# Famicom_IO_SNES_REV1_5.net
KiCad netlist of a schematic drawn in EAGLE
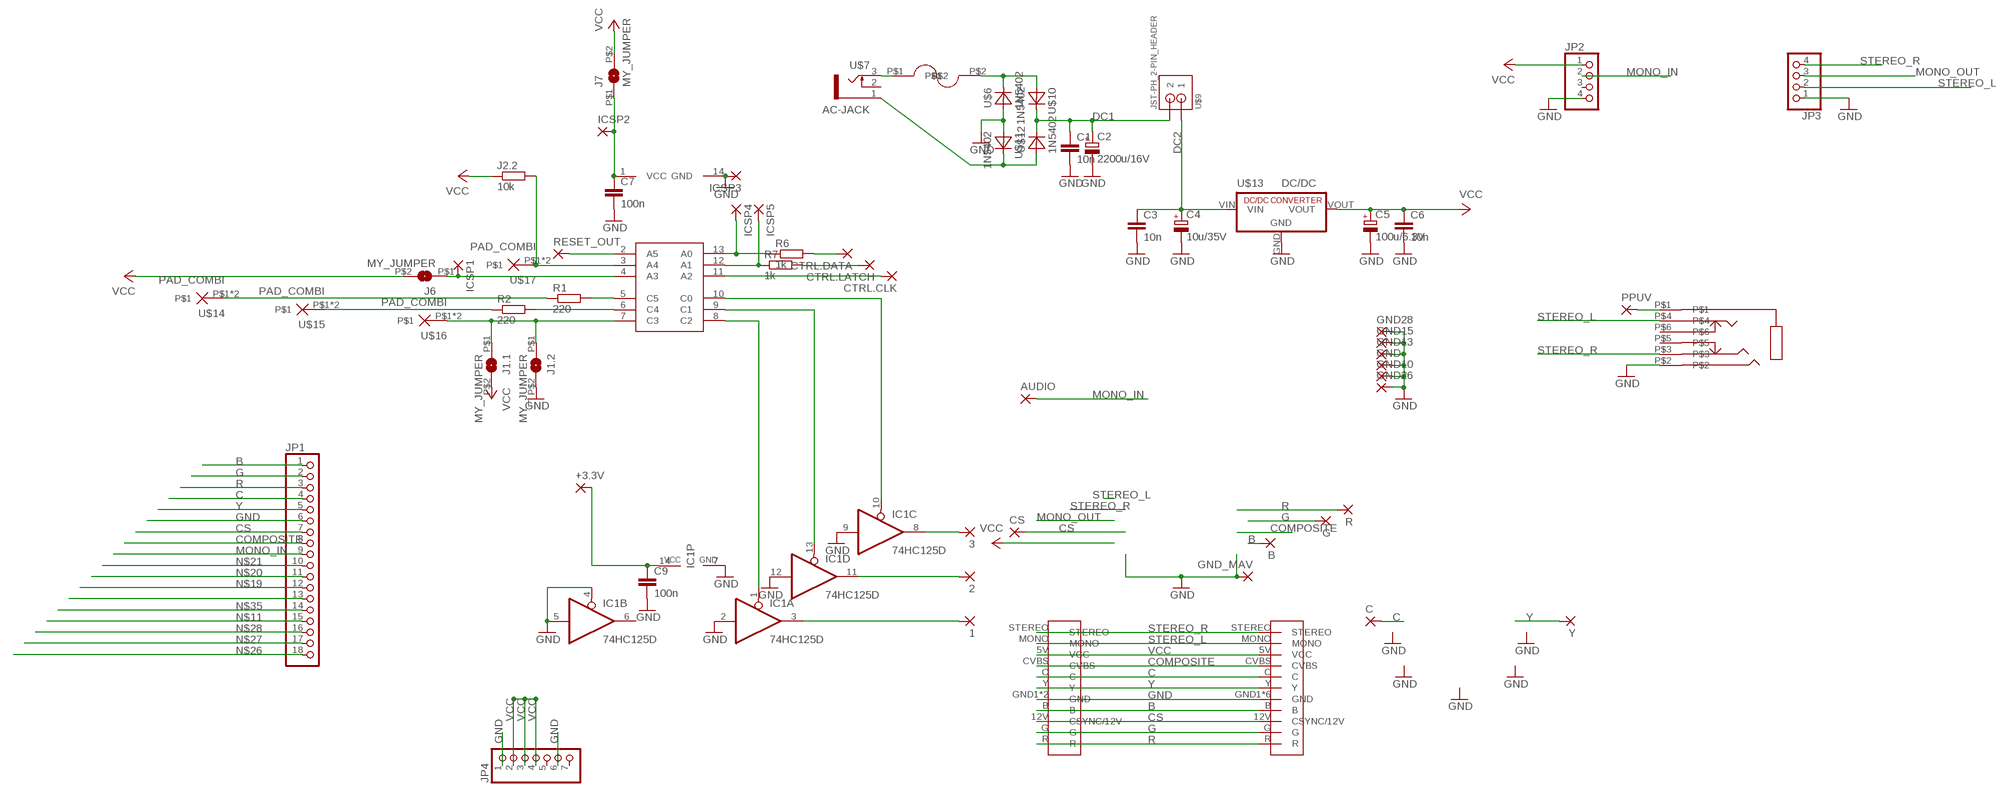
[diagram p0: schematic, sheet 1]

(export (version "E")
  (design (tool "Eeschema 10.0.6"))
  (components
    (comp (ref "+3.3V")
      (value "SMD2")
      (footprint "eagle-import:SMD1,27-2,54")
      (libsource (lib "eagle-import") (part "SMD2"))
    )
    (comp (ref "1")
      (value "SMD2")
      (footprint "eagle-import:SMD1,27-2,54")
      (libsource (lib "eagle-import") (part "SMD2"))
    )
    (comp (ref "2")
      (value "SMD2")
      (footprint "eagle-import:SMD1,27-2,54")
      (libsource (lib "eagle-import") (part "SMD2"))
    )
    (comp (ref "3")
      (value "SMD2")
      (footprint "eagle-import:SMD1,27-2,54")
      (libsource (lib "eagle-import") (part "SMD2"))
    )
    (comp (ref "AUDIO")
      (value "SMD2")
      (footprint "eagle-import:SMD1,27-2,54")
      (libsource (lib "eagle-import") (part "SMD2"))
    )
    (comp (ref "B")
      (value "SMD2")
      (footprint "eagle-import:SMD1,27-2,54")
      (libsource (lib "eagle-import") (part "SMD2"))
    )
    (comp (ref "C")
      (value "SMD2")
      (footprint "eagle-import:SMD1,27-2,54")
      (libsource (lib "eagle-import") (part "SMD2"))
    )
    (comp (ref "C1")
      (value "10n")
      (footprint "eagle-import:Z0805")
      (libsource (lib "eagle-import") (part "C0805"))
    )
    (comp (ref "C2")
      (value "2200u/16V")
      (footprint "eagle-import:E5-13")
      (libsource (lib "eagle-import") (part "resistor_CPOL-EUE5-13"))
    )
    (comp (ref "C3")
      (value "10n")
      (footprint "eagle-import:Z0805")
      (libsource (lib "eagle-import") (part "C0805"))
    )
    (comp (ref "C4")
      (value "10u/35V")
      (footprint "eagle-import:PANASONIC_B")
      (libsource (lib "eagle-import") (part "CPOL-EUB"))
    )
    (comp (ref "C5")
      (value "100u/6.3V")
      (footprint "eagle-import:PANASONIC_D")
      (libsource (lib "eagle-import") (part "CPOL-EUD"))
    )
    (comp (ref "C6")
      (value "10n")
      (footprint "eagle-import:Z0805")
      (libsource (lib "eagle-import") (part "C0805"))
    )
    (comp (ref "C7")
      (value "100n")
      (footprint "eagle-import:Z0805")
      (libsource (lib "eagle-import") (part "C0805"))
    )
    (comp (ref "C9")
      (value "100n")
      (footprint "eagle-import:Z0805")
      (libsource (lib "eagle-import") (part "C0805"))
    )
    (comp (ref "CS")
      (value "SMD2")
      (footprint "eagle-import:SMD1,27-2,54")
      (libsource (lib "eagle-import") (part "SMD2"))
    )
    (comp (ref "CTRL.CLK")
      (value "SMD2")
      (footprint "eagle-import:SMD1,27-2,54")
      (libsource (lib "eagle-import") (part "SMD2"))
    )
    (comp (ref "CTRL.DATA")
      (value "SMD2")
      (footprint "eagle-import:SMD1,27-2,54")
      (libsource (lib "eagle-import") (part "SMD2"))
    )
    (comp (ref "CTRL.LATCH")
      (value "SMD2")
      (footprint "eagle-import:SMD1,27-2,54")
      (libsource (lib "eagle-import") (part "SMD2"))
    )
    (comp (ref "G")
      (value "SMD2")
      (footprint "eagle-import:SMD1,27-2,54")
      (libsource (lib "eagle-import") (part "SMD2"))
    )
    (comp (ref "GND")
      (value "SMD5")
      (footprint "eagle-import:SMD2,54-5,08")
      (libsource (lib "eagle-import") (part "SMD5"))
    )
    (comp (ref "GND10")
      (value "SMD5")
      (footprint "eagle-import:SMD2,54-5,08")
      (libsource (lib "eagle-import") (part "SMD5"))
    )
    (comp (ref "GND13")
      (value "SMD5")
      (footprint "eagle-import:SMD2,54-5,08")
      (libsource (lib "eagle-import") (part "SMD5"))
    )
    (comp (ref "GND15")
      (value "SMD5")
      (footprint "eagle-import:SMD2,54-5,08")
      (libsource (lib "eagle-import") (part "SMD5"))
    )
    (comp (ref "GND26")
      (value "SMD5")
      (footprint "eagle-import:SMD2,54-5,08")
      (libsource (lib "eagle-import") (part "SMD5"))
    )
    (comp (ref "GND28")
      (value "SMD5")
      (footprint "eagle-import:SMD2,54-5,08")
      (libsource (lib "eagle-import") (part "SMD5"))
    )
    (comp (ref "GND_MAV")
      (value "SMD2")
      (footprint "eagle-import:SMD1,27-2,54")
      (libsource (lib "eagle-import") (part "SMD2"))
    )
    (comp (ref "IC1")
      (value "74HC125D")
      (footprint "eagle-import:SO14")
      (libsource (lib "eagle-import") (part "74125DHC"))
    )
    (comp (ref "ICSP1")
      (value "1,6/0,8")
      (footprint "eagle-import:1,6_0,8")
      (libsource (lib "eagle-import") (part "1,6/0,8"))
    )
    (comp (ref "ICSP2")
      (value "1,6/0,8")
      (footprint "eagle-import:1,6_0,8")
      (libsource (lib "eagle-import") (part "1,6/0,8"))
    )
    (comp (ref "ICSP3")
      (value "1,6/0,8")
      (footprint "eagle-import:1,6_0,8")
      (libsource (lib "eagle-import") (part "1,6/0,8"))
    )
    (comp (ref "ICSP4")
      (value "1,6/0,8")
      (footprint "eagle-import:1,6_0,8")
      (libsource (lib "eagle-import") (part "1,6/0,8"))
    )
    (comp (ref "ICSP5")
      (value "1,6/0,8")
      (footprint "eagle-import:1,6_0,8")
      (libsource (lib "eagle-import") (part "1,6/0,8"))
    )
    (comp (ref "J1.1")
      (value "MY_JUMPER")
      (footprint "eagle-import:MYJUMP")
      (libsource (lib "eagle-import") (part "MY_JUMPER"))
    )
    (comp (ref "J1.2")
      (value "MY_JUMPER")
      (footprint "eagle-import:MYJUMP")
      (libsource (lib "eagle-import") (part "MY_JUMPER"))
    )
    (comp (ref "J2.2")
      (value "10k")
      (footprint "eagle-import:Z0805")
      (libsource (lib "eagle-import") (part "R0805"))
    )
    (comp (ref "J6")
      (value "MY_JUMPER")
      (footprint "eagle-import:MYJUMP")
      (libsource (lib "eagle-import") (part "MY_JUMPER"))
    )
    (comp (ref "J7")
      (value "MY_JUMPER")
      (footprint "eagle-import:MYJUMP")
      (libsource (lib "eagle-import") (part "MY_JUMPER"))
    )
    (comp (ref "JP1")
      (value "PINHD-1X18_2.00")
      (footprint "eagle-import:1X18M")
      (libsource (lib "eagle-import") (part "PINHD-1X18_2.00"))
    )
    (comp (ref "JP2")
      (value "PINHD-1X04_2.54-S")
      (footprint "eagle-import:1X04-S")
      (libsource (lib "eagle-import") (part "PINHD-1X04_2.54-S"))
    )
    (comp (ref "JP3")
      (value "PINHD-1X04_2.54-S")
      (footprint "eagle-import:1X04-S")
      (libsource (lib "eagle-import") (part "PINHD-1X04_2.54-S"))
    )
    (comp (ref "JP4")
      (value "PINHD-1X07_2.54-S")
      (footprint "eagle-import:1X07-S")
      (libsource (lib "eagle-import") (part "PINHD-1X07_2.54-S"))
    )
    (comp (ref "PPUV")
      (value "SMD2")
      (footprint "eagle-import:SMD1,27-2,54")
      (libsource (lib "eagle-import") (part "SMD2"))
    )
    (comp (ref "R")
      (value "SMD2")
      (footprint "eagle-import:SMD1,27-2,54")
      (libsource (lib "eagle-import") (part "SMD2"))
    )
    (comp (ref "R1")
      (value "220")
      (footprint "eagle-import:Z0805")
      (libsource (lib "eagle-import") (part "R0805"))
    )
    (comp (ref "R2")
      (value "220")
      (footprint "eagle-import:Z0805")
      (libsource (lib "eagle-import") (part "R0805"))
    )
    (comp (ref "R6")
      (value "1k")
      (footprint "eagle-import:Z0805")
      (libsource (lib "eagle-import") (part "R0805"))
    )
    (comp (ref "R7")
      (value "1k")
      (footprint "eagle-import:Z0805")
      (libsource (lib "eagle-import") (part "R0805"))
    )
    (comp (ref "RESET_OUT")
      (value "SMD2")
      (footprint "eagle-import:SMD1,27-2,54")
      (libsource (lib "eagle-import") (part "SMD2"))
    )
    (comp (ref "U$2")
      (value "FUSEHOLDER")
      (footprint "eagle-import:FUSEHOLDER")
      (libsource (lib "eagle-import") (part "FUSEHOLDER"))
    )
    (comp (ref "U$5")
      (value "PIC16F630_SIMPLE")
      (footprint "eagle-import:PIC16F630")
      (libsource (lib "eagle-import") (part "PIC16F630_SIMPLE"))
    )
    (comp (ref "U$6")
      (value "1N5402")
      (footprint "eagle-import:DO201")
      (libsource (lib "eagle-import") (part "1N5402"))
    )
    (comp (ref "U$7")
      (value "AC-JACK")
      (footprint "eagle-import:AC-JACK")
      (libsource (lib "eagle-import") (part "AC-JACK"))
    )
    (comp (ref "U$8")
      (value "PJ-342D")
      (footprint "eagle-import:PJ-342")
      (libsource (lib "eagle-import") (part "PJ-342D"))
    )
    (comp (ref "U$9")
      (value "JST-PH_2-PIN_HEADER")
      (footprint "eagle-import:JST_B2B-PH_HEADER")
      (libsource (lib "eagle-import") (part "JST-PH_2-PIN_HEADER"))
    )
    (comp (ref "U$10")
      (value "1N5402")
      (footprint "eagle-import:DO201")
      (libsource (lib "eagle-import") (part "1N5402"))
    )
    (comp (ref "U$11")
      (value "1N5402")
      (footprint "eagle-import:DO201")
      (libsource (lib "eagle-import") (part "1N5402"))
    )
    (comp (ref "U$12")
      (value "1N5402")
      (footprint "eagle-import:DO201")
      (libsource (lib "eagle-import") (part "1N5402"))
    )
    (comp (ref "U$13")
      (value "DC/DC")
      (footprint "eagle-import:RECOM")
      (libsource (lib "eagle-import") (part "DC/DC"))
    )
    (comp (ref "U$14")
      (value "PAD_COMBI")
      (footprint "eagle-import:PAD_COMBI")
      (libsource (lib "eagle-import") (part "PAD_COMBI"))
    )
    (comp (ref "U$15")
      (value "PAD_COMBI")
      (footprint "eagle-import:PAD_COMBI")
      (libsource (lib "eagle-import") (part "PAD_COMBI"))
    )
    (comp (ref "U$16")
      (value "PAD_COMBI")
      (footprint "eagle-import:PAD_COMBI")
      (libsource (lib "eagle-import") (part "PAD_COMBI"))
    )
    (comp (ref "U$17")
      (value "PAD_COMBI")
      (footprint "eagle-import:PAD_COMBI")
      (libsource (lib "eagle-import") (part "PAD_COMBI"))
    )
    (comp (ref "U$19")
      (value "GC-MULTIAV")
      (footprint "eagle-import:GC-MULTIAV")
      (libsource (lib "eagle-import") (part "GC-MULTIAV"))
    )
    (comp (ref "U$20")
      (value "SNES-MULTIAV2")
      (footprint "eagle-import:SNES-MULTIAV2")
      (libsource (lib "eagle-import") (part "SNES-MULTIAV2"))
    )
    (comp (ref "Y")
      (value "SMD2")
      (footprint "eagle-import:SMD1,27-2,54")
      (libsource (lib "eagle-import") (part "SMD2"))
    )
  )
  (nets
    (net (code "1") (name "/B") (class "Default")
      (node (ref "B") (pin "1") (pinfunction "P_1") (pintype "passive"))
      (node (ref "JP1") (pin "1") (pinfunction "1_1") (pintype "passive"))
      (node (ref "U$19") (pin "B") (pinfunction "B_B") (pintype "output"))
      (node (ref "U$20") (pin "B") (pinfunction "B_B") (pintype "output"))
    )
    (net (code "2") (name "/C") (class "Default")
      (node (ref "C") (pin "1") (pinfunction "P_1") (pintype "passive"))
      (node (ref "JP1") (pin "4") (pinfunction "4_4") (pintype "passive"))
      (node (ref "U$19") (pin "C") (pinfunction "C_C") (pintype "output"))
      (node (ref "U$20") (pin "C") (pinfunction "C_C") (pintype "output"))
    )
    (net (code "3") (name "/COMPOSITE") (class "Default")
      (node (ref "JP1") (pin "8") (pinfunction "8_8") (pintype "passive"))
      (node (ref "PPUV") (pin "1") (pinfunction "P_1") (pintype "passive"))
      (node (ref "U$19") (pin "CVBS") (pinfunction "CVBS_CVBS") (pintype "output"))
      (node (ref "U$20") (pin "CVBS") (pinfunction "CVBS_CVBS") (pintype "output"))
      (node (ref "U$8") (pin "P$1") (pinfunction "P$1_P$1") (pintype "bidirectional"))
    )
    (net (code "4") (name "/CS") (class "Default")
      (node (ref "CS") (pin "1") (pinfunction "P_1") (pintype "passive"))
      (node (ref "JP1") (pin "7") (pinfunction "7_7") (pintype "passive"))
      (node (ref "U$19") (pin "12V") (pinfunction "CSYNC/12V_12V") (pintype "output"))
      (node (ref "U$20") (pin "12V") (pinfunction "CSYNC/12V_12V") (pintype "output"))
    )
    (net (code "5") (name "/DC1") (class "Default")
      (node (ref "C1") (pin "1") (pinfunction "1_1") (pintype "passive"))
      (node (ref "C2") (pin "+") (pinfunction "+_+") (pintype "passive"))
      (node (ref "U$10") (pin "C") (pinfunction "C_C") (pintype "passive"))
      (node (ref "U$12") (pin "C") (pinfunction "C_C") (pintype "passive"))
      (node (ref "U$9") (pin "P2") (pinfunction "2_P2") (pintype "bidirectional"))
    )
    (net (code "6") (name "/DC2") (class "Default")
      (node (ref "C3") (pin "1") (pinfunction "1_1") (pintype "passive"))
      (node (ref "C4") (pin "+") (pinfunction "+_+") (pintype "passive"))
      (node (ref "U$13") (pin "VIN") (pinfunction "VIN_VIN") (pintype "passive"))
      (node (ref "U$9") (pin "P1") (pinfunction "1_P1") (pintype "bidirectional"))
    )
    (net (code "7") (name "/G") (class "Default")
      (node (ref "G") (pin "1") (pinfunction "P_1") (pintype "passive"))
      (node (ref "JP1") (pin "2") (pinfunction "2_2") (pintype "passive"))
      (node (ref "U$19") (pin "G") (pinfunction "G_G") (pintype "output"))
      (node (ref "U$20") (pin "G") (pinfunction "G_G") (pintype "output"))
    )
    (net (code "8") (name "/MONO_IN") (class "Default")
      (node (ref "AUDIO") (pin "1") (pinfunction "P_1") (pintype "passive"))
      (node (ref "JP1") (pin "9") (pinfunction "9_9") (pintype "passive"))
      (node (ref "JP2") (pin "2") (pinfunction "2_2") (pintype "passive"))
    )
    (net (code "9") (name "/MONO_OUT") (class "Default")
      (node (ref "JP3") (pin "3") (pinfunction "3_3") (pintype "passive"))
    )
    (net (code "10") (name "/N$11") (class "Default")
      (node (ref "3") (pin "1") (pinfunction "P_1") (pintype "passive"))
      (node (ref "IC1") (pin "8") (pinfunction "O_8") (pintype "tri_state"))
      (node (ref "JP1") (pin "15") (pinfunction "15_15") (pintype "passive"))
    )
    (net (code "11") (name "/N$19") (class "Default")
      (node (ref "CTRL.DATA") (pin "1") (pinfunction "P_1") (pintype "passive"))
      (node (ref "JP1") (pin "12") (pinfunction "12_12") (pintype "passive"))
      (node (ref "R6") (pin "2") (pinfunction "2_2") (pintype "passive"))
    )
    (net (code "12") (name "/N$20") (class "Default")
      (node (ref "CTRL.LATCH") (pin "1") (pinfunction "P_1") (pintype "passive"))
      (node (ref "JP1") (pin "11") (pinfunction "11_11") (pintype "passive"))
      (node (ref "R7") (pin "2") (pinfunction "2_2") (pintype "passive"))
    )
    (net (code "13") (name "/N$21") (class "Default")
      (node (ref "CTRL.CLK") (pin "1") (pinfunction "P_1") (pintype "passive"))
      (node (ref "JP1") (pin "10") (pinfunction "10_10") (pintype "passive"))
      (node (ref "U$5") (pin "11") (pinfunction "A2_11") (pintype "bidirectional"))
    )
    (net (code "14") (name "/N$26") (class "Default")
      (node (ref "+3.3V") (pin "1") (pinfunction "P_1") (pintype "passive"))
      (node (ref "C9") (pin "1") (pinfunction "1_1") (pintype "passive"))
      (node (ref "IC1") (pin "14") (pinfunction "VCC_14") (pintype "power_in"))
      (node (ref "JP1") (pin "18") (pinfunction "18_18") (pintype "passive"))
    )
    (net (code "15") (name "/N$27") (class "Default")
      (node (ref "1") (pin "1") (pinfunction "P_1") (pintype "passive"))
      (node (ref "IC1") (pin "3") (pinfunction "O_3") (pintype "tri_state"))
      (node (ref "JP1") (pin "17") (pinfunction "17_17") (pintype "passive"))
    )
    (net (code "16") (name "/N$28") (class "Default")
      (node (ref "2") (pin "1") (pinfunction "P_1") (pintype "passive"))
      (node (ref "IC1") (pin "11") (pinfunction "O_11") (pintype "tri_state"))
      (node (ref "JP1") (pin "16") (pinfunction "16_16") (pintype "passive"))
    )
    (net (code "17") (name "/N$35") (class "Default")
      (node (ref "JP1") (pin "14") (pinfunction "14_14") (pintype "passive"))
      (node (ref "RESET_OUT") (pin "1") (pinfunction "P_1") (pintype "passive"))
      (node (ref "U$5") (pin "2") (pinfunction "A5_2") (pintype "bidirectional"))
    )
    (net (code "18") (name "/R") (class "Default")
      (node (ref "JP1") (pin "3") (pinfunction "3_3") (pintype "passive"))
      (node (ref "R") (pin "1") (pinfunction "P_1") (pintype "passive"))
      (node (ref "U$19") (pin "R") (pinfunction "R_R") (pintype "output"))
      (node (ref "U$20") (pin "R") (pinfunction "R_R") (pintype "output"))
    )
    (net (code "19") (name "/STEREO_L") (class "Default")
      (node (ref "JP3") (pin "2") (pinfunction "2_2") (pintype "passive"))
      (node (ref "U$19") (pin "MONO") (pinfunction "MONO_MONO") (pintype "output"))
      (node (ref "U$20") (pin "MONO") (pinfunction "MONO_MONO") (pintype "output"))
      (node (ref "U$8") (pin "P$4") (pinfunction "P$4_P$4") (pintype "bidirectional"))
    )
    (net (code "20") (name "/STEREO_R") (class "Default")
      (node (ref "JP3") (pin "4") (pinfunction "4_4") (pintype "passive"))
      (node (ref "U$19") (pin "STEREO") (pinfunction "STEREO_STEREO") (pintype "output"))
      (node (ref "U$20") (pin "STEREO") (pinfunction "STEREO_STEREO") (pintype "output"))
      (node (ref "U$8") (pin "P$3") (pinfunction "P$3_P$3") (pintype "bidirectional"))
    )
    (net (code "21") (name "/Y") (class "Default")
      (node (ref "JP1") (pin "5") (pinfunction "5_5") (pintype "passive"))
      (node (ref "U$19") (pin "Y") (pinfunction "Y_Y") (pintype "output"))
      (node (ref "U$20") (pin "Y") (pinfunction "Y_Y") (pintype "output"))
      (node (ref "Y") (pin "1") (pinfunction "P_1") (pintype "passive"))
    )
    (net (code "22") (name "GND") (class "Default")
      (node (ref "C1") (pin "2") (pinfunction "2_2") (pintype "passive"))
      (node (ref "C2") (pin "-") (pinfunction "-_-") (pintype "passive"))
      (node (ref "C3") (pin "2") (pinfunction "2_2") (pintype "passive"))
      (node (ref "C4") (pin "-") (pinfunction "-_-") (pintype "passive"))
      (node (ref "C5") (pin "-") (pinfunction "-_-") (pintype "passive"))
      (node (ref "C6") (pin "2") (pinfunction "2_2") (pintype "passive"))
      (node (ref "C7") (pin "2") (pinfunction "2_2") (pintype "passive"))
      (node (ref "C9") (pin "2") (pinfunction "2_2") (pintype "passive"))
      (node (ref "GND") (pin "1") (pinfunction "P_1") (pintype "passive"))
      (node (ref "GND10") (pin "1") (pinfunction "P_1") (pintype "passive"))
      (node (ref "GND13") (pin "1") (pinfunction "P_1") (pintype "passive"))
      (node (ref "GND15") (pin "1") (pinfunction "P_1") (pintype "passive"))
      (node (ref "GND26") (pin "1") (pinfunction "P_1") (pintype "passive"))
      (node (ref "GND28") (pin "1") (pinfunction "P_1") (pintype "passive"))
      (node (ref "GND_MAV") (pin "1") (pinfunction "P_1") (pintype "passive"))
      (node (ref "IC1") (pin "12") (pinfunction "I_12") (pintype "input"))
      (node (ref "IC1") (pin "2") (pinfunction "I_2") (pintype "input"))
      (node (ref "IC1") (pin "4") (pinfunction "OE_4") (pintype "input"))
      (node (ref "IC1") (pin "5") (pinfunction "I_5") (pintype "input"))
      (node (ref "IC1") (pin "7") (pinfunction "GND_7") (pintype "power_in"))
      (node (ref "IC1") (pin "9") (pinfunction "I_9") (pintype "input"))
      (node (ref "ICSP3") (pin "1") (pinfunction "P_1") (pintype "passive"))
      (node (ref "J1.2") (pin "P$2") (pinfunction "2_P$2") (pintype "passive"))
      (node (ref "JP1") (pin "6") (pinfunction "6_6") (pintype "passive"))
      (node (ref "JP2") (pin "4") (pinfunction "4_4") (pintype "passive"))
      (node (ref "JP3") (pin "1") (pinfunction "1_1") (pintype "passive"))
      (node (ref "JP4") (pin "1") (pinfunction "1_1") (pintype "passive"))
      (node (ref "JP4") (pin "6") (pinfunction "6_6") (pintype "passive"))
      (node (ref "U$11") (pin "A") (pinfunction "A_A") (pintype "passive"))
      (node (ref "U$13") (pin "GND") (pinfunction "GND_GND") (pintype "passive"))
      (node (ref "U$19") (pin "GND1") (pinfunction "GND_GND1") (pintype "output"))
      (node (ref "U$19") (pin "GND2") (pinfunction "GND_GND2") (pintype "output"))
      (node (ref "U$19") (pin "GND3") (pinfunction "GND_GND3") (pintype "output"))
      (node (ref "U$19") (pin "GND4") (pinfunction "GND_GND4") (pintype "output"))
      (node (ref "U$19") (pin "GND5") (pinfunction "GND_GND5") (pintype "output"))
      (node (ref "U$19") (pin "GND6") (pinfunction "GND_GND6") (pintype "output"))
      (node (ref "U$20") (pin "GND1") (pinfunction "GND_GND1") (pintype "output"))
      (node (ref "U$20") (pin "GND2") (pinfunction "GND_GND2") (pintype "output"))
      (node (ref "U$5") (pin "14") (pinfunction "GND_14") (pintype "bidirectional"))
      (node (ref "U$6") (pin "A") (pinfunction "A_A") (pintype "passive"))
      (node (ref "U$8") (pin "P$2") (pinfunction "P$2_P$2") (pintype "bidirectional"))
    )
    (net (code "23") (name "Net-(IC1A-OE)") (class "Default")
      (node (ref "IC1") (pin "1") (pinfunction "OE_1") (pintype "input"))
      (node (ref "U$5") (pin "8") (pinfunction "C2_8") (pintype "bidirectional"))
    )
    (net (code "24") (name "Net-(IC1C-OE)") (class "Default")
      (node (ref "IC1") (pin "10") (pinfunction "OE_10") (pintype "input"))
      (node (ref "U$5") (pin "10") (pinfunction "C0_10") (pintype "bidirectional"))
    )
    (net (code "25") (name "Net-(IC1D-OE)") (class "Default")
      (node (ref "IC1") (pin "13") (pinfunction "OE_13") (pintype "input"))
      (node (ref "U$5") (pin "9") (pinfunction "C1_9") (pintype "bidirectional"))
    )
    (net (code "26") (name "Net-(ICSP1-P)") (class "Default")
      (node (ref "ICSP1") (pin "1") (pinfunction "P_1") (pintype "passive"))
      (node (ref "J6") (pin "P$1") (pinfunction "1_P$1") (pintype "passive"))
      (node (ref "U$5") (pin "4") (pinfunction "A3_4") (pintype "bidirectional"))
    )
    (net (code "27") (name "Net-(ICSP2-P)") (class "Default")
      (node (ref "C7") (pin "1") (pinfunction "1_1") (pintype "passive"))
      (node (ref "ICSP2") (pin "1") (pinfunction "P_1") (pintype "passive"))
      (node (ref "J7") (pin "P$1") (pinfunction "1_P$1") (pintype "passive"))
      (node (ref "U$5") (pin "1") (pinfunction "VCC_1") (pintype "bidirectional"))
    )
    (net (code "28") (name "Net-(ICSP4-P)") (class "Default")
      (node (ref "ICSP4") (pin "1") (pinfunction "P_1") (pintype "passive"))
      (node (ref "R6") (pin "1") (pinfunction "1_1") (pintype "passive"))
      (node (ref "U$5") (pin "13") (pinfunction "A0_13") (pintype "bidirectional"))
    )
    (net (code "29") (name "Net-(ICSP5-P)") (class "Default")
      (node (ref "ICSP5") (pin "1") (pinfunction "P_1") (pintype "passive"))
      (node (ref "R7") (pin "1") (pinfunction "1_1") (pintype "passive"))
      (node (ref "U$5") (pin "12") (pinfunction "A1_12") (pintype "bidirectional"))
    )
    (net (code "30") (name "Net-(J1.1-1)") (class "Default")
      (node (ref "J1.1") (pin "P$1") (pinfunction "1_P$1") (pintype "passive"))
      (node (ref "J1.2") (pin "P$1") (pinfunction "1_P$1") (pintype "passive"))
      (node (ref "U$16") (pin "P$1") (pinfunction "P$1_P$1") (pintype "bidirectional"))
      (node (ref "U$16") (pin "P$2") (pinfunction "P$1_P$2") (pintype "bidirectional"))
      (node (ref "U$5") (pin "7") (pinfunction "C3_7") (pintype "bidirectional"))
    )
    (net (code "31") (name "Net-(R1-Pad1)") (class "Default")
      (node (ref "R1") (pin "1") (pinfunction "1_1") (pintype "passive"))
      (node (ref "U$14") (pin "P$1") (pinfunction "P$1_P$1") (pintype "bidirectional"))
      (node (ref "U$14") (pin "P$2") (pinfunction "P$1_P$2") (pintype "bidirectional"))
    )
    (net (code "32") (name "Net-(R2-Pad1)") (class "Default")
      (node (ref "R2") (pin "1") (pinfunction "1_1") (pintype "passive"))
      (node (ref "U$15") (pin "P$1") (pinfunction "P$1_P$1") (pintype "bidirectional"))
      (node (ref "U$15") (pin "P$2") (pinfunction "P$1_P$2") (pintype "bidirectional"))
    )
    (net (code "33") (name "Net-(U$2-PadP$1)") (class "Default")
      (node (ref "U$2") (pin "P$1") (pinfunction "P$1_P$1") (pintype "bidirectional"))
      (node (ref "U$7") (pin "3") (pinfunction "3_3") (pintype "passive"))
    )
    (net (code "34") (name "Net-(U$5A-A4)") (class "Default")
      (node (ref "J2.2") (pin "2") (pinfunction "2_2") (pintype "passive"))
      (node (ref "U$17") (pin "P$1") (pinfunction "P$1_P$1") (pintype "bidirectional"))
      (node (ref "U$17") (pin "P$2") (pinfunction "P$1_P$2") (pintype "bidirectional"))
      (node (ref "U$5") (pin "3") (pinfunction "A4_3") (pintype "bidirectional"))
    )
    (net (code "35") (name "Net-(U$5A-C4)") (class "Default")
      (node (ref "R2") (pin "2") (pinfunction "2_2") (pintype "passive"))
      (node (ref "U$5") (pin "6") (pinfunction "C4_6") (pintype "bidirectional"))
    )
    (net (code "36") (name "Net-(U$5A-C5)") (class "Default")
      (node (ref "R1") (pin "2") (pinfunction "2_2") (pintype "passive"))
      (node (ref "U$5") (pin "5") (pinfunction "C5_5") (pintype "bidirectional"))
    )
    (net (code "37") (name "Net-(U$7-5)") (class "Default")
      (node (ref "U$11") (pin "C") (pinfunction "C_C") (pintype "passive"))
      (node (ref "U$12") (pin "A") (pinfunction "A_A") (pintype "passive"))
      (node (ref "U$7") (pin "1") (pinfunction "5_1") (pintype "passive"))
    )
    (net (code "38") (name "Net-(U$10-PadA)") (class "Default")
      (node (ref "U$10") (pin "A") (pinfunction "A_A") (pintype "passive"))
      (node (ref "U$2") (pin "P$2") (pinfunction "P$2_P$2") (pintype "bidirectional"))
      (node (ref "U$6") (pin "C") (pinfunction "C_C") (pintype "passive"))
    )
    (net (code "39") (name "VCC") (class "Default")
      (node (ref "C5") (pin "+") (pinfunction "+_+") (pintype "passive"))
      (node (ref "C6") (pin "1") (pinfunction "1_1") (pintype "passive"))
      (node (ref "J1.1") (pin "P$2") (pinfunction "2_P$2") (pintype "passive"))
      (node (ref "J2.2") (pin "1") (pinfunction "1_1") (pintype "passive"))
      (node (ref "J6") (pin "P$2") (pinfunction "2_P$2") (pintype "passive"))
      (node (ref "J7") (pin "P$2") (pinfunction "2_P$2") (pintype "passive"))
      (node (ref "JP2") (pin "1") (pinfunction "1_1") (pintype "passive"))
      (node (ref "JP4") (pin "2") (pinfunction "2_2") (pintype "passive"))
      (node (ref "JP4") (pin "3") (pinfunction "3_3") (pintype "passive"))
      (node (ref "JP4") (pin "4") (pinfunction "4_4") (pintype "passive"))
      (node (ref "U$13") (pin "VOUT") (pinfunction "VOUT_VOUT") (pintype "passive"))
      (node (ref "U$19") (pin "5V") (pinfunction "VCC_5V") (pintype "output"))
      (node (ref "U$20") (pin "5V") (pinfunction "VCC_5V") (pintype "output"))
    )
    (net (code "40") (name "unconnected-(IC1B-O-Pad6)") (class "Default")
      (node (ref "IC1") (pin "6") (pinfunction "O_6") (pintype "tri_state"))
    )
    (net (code "41") (name "unconnected-(JP1-Pad13)") (class "Default")
      (node (ref "JP1") (pin "13") (pinfunction "13_13") (pintype "passive"))
    )
    (net (code "42") (name "unconnected-(JP2-Pad3)") (class "Default")
      (node (ref "JP2") (pin "3") (pinfunction "3_3") (pintype "passive"))
    )
    (net (code "43") (name "unconnected-(JP4-Pad5)") (class "Default")
      (node (ref "JP4") (pin "5") (pinfunction "5_5") (pintype "passive"))
    )
    (net (code "44") (name "unconnected-(JP4-Pad7)") (class "Default")
      (node (ref "JP4") (pin "7") (pinfunction "7_7") (pintype "passive"))
    )
    (net (code "45") (name "unconnected-(U$7-4-Pad2)") (class "Default")
      (node (ref "U$7") (pin "2") (pinfunction "4_2") (pintype "passive"))
    )
    (net (code "46") (name "unconnected-(U$8-PadP$5)") (class "Default")
      (node (ref "U$8") (pin "P$5") (pinfunction "P$5_P$5") (pintype "bidirectional"))
    )
    (net (code "47") (name "unconnected-(U$8-PadP$6)") (class "Default")
      (node (ref "U$8") (pin "P$6") (pinfunction "P$6_P$6") (pintype "bidirectional"))
    )
  )
)
